# 2-RJ45.net
KiCad netlist of a schematic drawn in Altium Designer
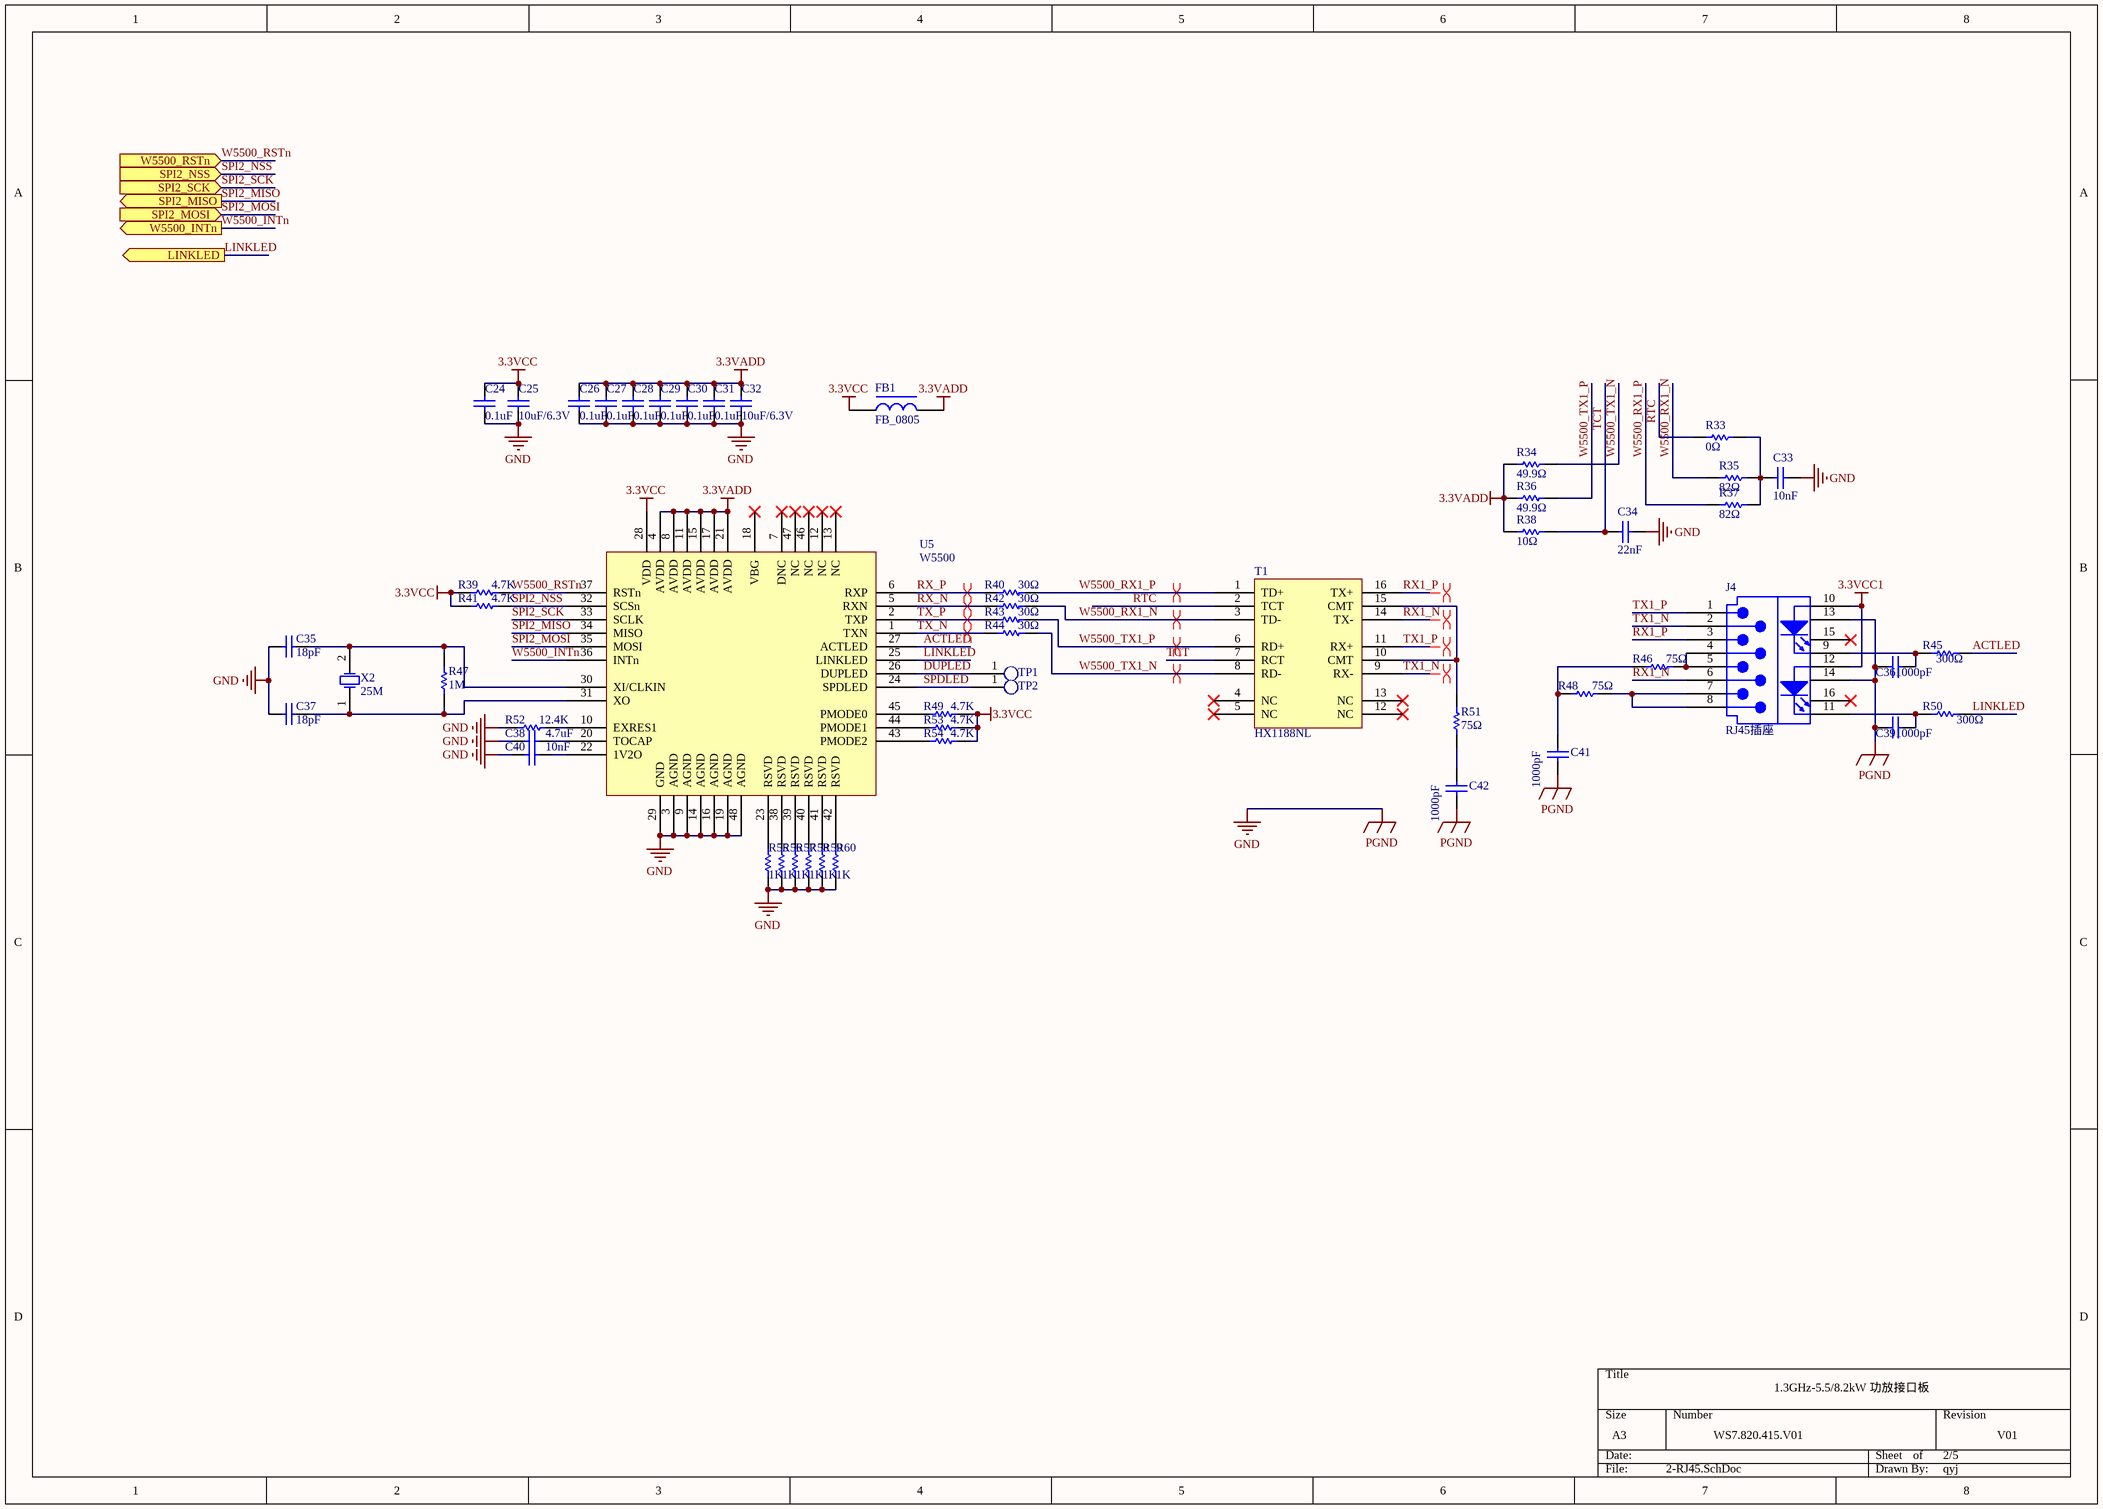
[diagram p0: 2-RJ45.SchDoc]

(export (version "E")
  (design (tool "Eeschema 10.0.6"))
  (components
    (comp (ref "C24")
      (value "0.1uF")
      (footprint "C0603")
      (description "贴片电容_GRM188R71H104KA01D_0.1uF±10%,50V,0603")
      (libsource (lib "20贴片电容0603") (part "0.1uF贴片电容"))
    )
    (comp (ref "C25")
      (value "10uF/6.3V")
      (footprint "C0603")
      (description "贴片电容_GRM188R60J106ME47D_10uF±20%,6.3V,0603")
      (libsource (lib "20贴片电容0603") (part "10uF贴片电容"))
    )
    (comp (ref "C26")
      (value "0.1uF")
      (footprint "C0603")
      (description "贴片电容_GRM188R71H104KA01D_0.1uF±10%,50V,0603")
      (libsource (lib "20贴片电容0603") (part "0.1uF贴片电容"))
    )
    (comp (ref "C27")
      (value "0.1uF")
      (footprint "C0603")
      (description "贴片电容_GRM188R71H104KA01D_0.1uF±10%,50V,0603")
      (libsource (lib "20贴片电容0603") (part "0.1uF贴片电容"))
    )
    (comp (ref "C28")
      (value "0.1uF")
      (footprint "C0603")
      (description "贴片电容_GRM188R71H104KA01D_0.1uF±10%,50V,0603")
      (libsource (lib "20贴片电容0603") (part "0.1uF贴片电容"))
    )
    (comp (ref "C29")
      (value "0.1uF")
      (footprint "C0603")
      (description "贴片电容_GRM188R71H104KA01D_0.1uF±10%,50V,0603")
      (libsource (lib "20贴片电容0603") (part "0.1uF贴片电容"))
    )
    (comp (ref "C30")
      (value "0.1uF")
      (footprint "C0603")
      (description "贴片电容_GRM188R71H104KA01D_0.1uF±10%,50V,0603")
      (libsource (lib "20贴片电容0603") (part "0.1uF贴片电容"))
    )
    (comp (ref "C31")
      (value "0.1uF")
      (footprint "C0603")
      (description "贴片电容_GRM188R71H104KA01D_0.1uF±10%,50V,0603")
      (libsource (lib "20贴片电容0603") (part "0.1uF贴片电容"))
    )
    (comp (ref "C32")
      (value "10uF/6.3V")
      (footprint "C0603")
      (description "贴片电容_GRM188R60J106ME47D_10uF±20%,6.3V,0603")
      (libsource (lib "20贴片电容0603") (part "10uF贴片电容"))
    )
    (comp (ref "C33")
      (value "10nF")
      (footprint "C0603")
      (description "C0603C103K5RAC_10nF±10%,50V,0603")
      (fields (field (name "MPN") "KEMET"))
      (libsource (lib "20贴片电容0603") (part "0.1uF贴片电容"))
    )
    (comp (ref "C34")
      (value "22nF")
      (footprint "C0603")
      (description "贴片电容_22nF±5%,50V,0603")
      (libsource (lib "20贴片电容0603") (part "27nF贴片电容"))
    )
    (comp (ref "C35")
      (value "18pF")
      (footprint "C0603")
      (description "贴片电容_GRM1885C1H180JA01D_18pF±5%,50V,0603")
      (libsource (lib "20贴片电容0603") (part "18pF贴片电容"))
    )
    (comp (ref "C36")
      (value "1000pF")
      (footprint "C0603")
      (description "贴片电容_GRM188R71H102KA01_1000pF±10%,50V,0603")
      (libsource (lib "20贴片电容0603") (part "1000pF贴片电容"))
    )
    (comp (ref "C37")
      (value "18pF")
      (footprint "C0603")
      (description "贴片电容_GRM1885C1H180JA01D_18pF±5%,50V,0603")
      (libsource (lib "20贴片电容0603") (part "18pF贴片电容"))
    )
    (comp (ref "C38")
      (value "4.7uF")
      (footprint "C0603")
      (description "GRM188R61C475K_4.7uF±10%,16V,0603")
      (fields (field (name "MPN") "Murata"))
      (libsource (lib "20贴片电容0603") (part "1uF贴片电容"))
    )
    (comp (ref "C39")
      (value "1000pF")
      (footprint "C0603")
      (description "贴片电容_GRM188R71H102KA01_1000pF±10%,50V,0603")
      (libsource (lib "20贴片电容0603") (part "1000pF贴片电容"))
    )
    (comp (ref "C40")
      (value "10nF")
      (footprint "C0603")
      (description "C0603C103K5RAC_10nF±10%,50V,0603")
      (fields (field (name "MPN") "KEMET"))
      (libsource (lib "20贴片电容0603") (part "0.1uF贴片电容"))
    )
    (comp (ref "C41")
      (value "1000pF")
      (footprint "C1206")
      (description "贴片电容_C1206C102J5GAC _1000pF±5%,50V,1206")
      (fields (field (name "MPN") "KEMET"))
      (libsource (lib "22贴片电容1210") (part "10uF贴片电容"))
    )
    (comp (ref "C42")
      (value "1000pF")
      (footprint "C1206")
      (description "贴片电容_C1206C102J5GAC _1000pF±5%,50V,1206")
      (fields (field (name "MPN") "KEMET"))
      (libsource (lib "22贴片电容1210") (part "10uF贴片电容"))
    )
    (comp (ref "FB1")
      (value "FB_0805")
      (footprint "L0805")
      (description "贴片磁珠_600R,0805")
      (libsource (lib "32贴片磁珠0805") (part "0805贴片磁珠"))
    )
    (comp (ref "J4")
      (value "RJ45插座")
      (footprint "RJ45TH-1x1-2R54-LED")
      (description "RJ45插座_1*1,带左黄右绿灯,弯脚")
      (fields (field (name "MPN") "朱迅"))
      (libsource (lib "91连接器") (part "RJ45弯脚带灯"))
    )
    (comp (ref "R33")
      (value "0Ω")
      (footprint "R0603")
      (description "贴片电阻_0Ω±5%,0603")
      (libsource (lib "10贴片电阻0603") (part "0Ω贴片电阻"))
    )
    (comp (ref "R34")
      (value "49.9Ω")
      (footprint "R0603")
      (description "贴片电阻_49.9Ω±1%,0603")
      (libsource (lib "10贴片电阻0603") (part "51Ω贴片电阻"))
    )
    (comp (ref "R35")
      (value "82Ω")
      (footprint "R0603")
      (description "贴片电阻_82Ω±1%,0603")
      (libsource (lib "10贴片电阻0603") (part "51Ω贴片电阻"))
    )
    (comp (ref "R36")
      (value "49.9Ω")
      (footprint "R0603")
      (description "贴片电阻_49.9Ω±1%,0603")
      (libsource (lib "10贴片电阻0603") (part "51Ω贴片电阻"))
    )
    (comp (ref "R37")
      (value "82Ω")
      (footprint "R0603")
      (description "贴片电阻_82Ω±1%,0603")
      (libsource (lib "10贴片电阻0603") (part "51Ω贴片电阻"))
    )
    (comp (ref "R38")
      (value "10Ω")
      (footprint "R0603")
      (description "贴片电阻_10Ω±5%,0603")
      (libsource (lib "10贴片电阻0603") (part "10Ω贴片电阻"))
    )
    (comp (ref "R39")
      (value "4.7K")
      (footprint "R0603")
      (description "贴片电阻_4.7K±5%,0603")
      (libsource (lib "10贴片电阻0603") (part "4.7K贴片电阻"))
    )
    (comp (ref "R40")
      (value "30Ω")
      (footprint "R0603")
      (description "贴片电阻_30Ω±5%,0603")
      (libsource (lib "10贴片电阻0603") (part "30Ω贴片电阻"))
    )
    (comp (ref "R41")
      (value "4.7K")
      (footprint "R0603")
      (description "贴片电阻_4.7K±5%,0603")
      (libsource (lib "10贴片电阻0603") (part "4.7K贴片电阻"))
    )
    (comp (ref "R42")
      (value "30Ω")
      (footprint "R0603")
      (description "贴片电阻_30Ω±5%,0603")
      (libsource (lib "10贴片电阻0603") (part "30Ω贴片电阻"))
    )
    (comp (ref "R43")
      (value "30Ω")
      (footprint "R0603")
      (description "贴片电阻_30Ω±5%,0603")
      (libsource (lib "10贴片电阻0603") (part "30Ω贴片电阻"))
    )
    (comp (ref "R44")
      (value "30Ω")
      (footprint "R0603")
      (description "贴片电阻_30Ω±5%,0603")
      (libsource (lib "10贴片电阻0603") (part "30Ω贴片电阻"))
    )
    (comp (ref "R45")
      (value "300Ω")
      (footprint "R0603")
      (description "贴片电阻_300Ω±5%,0603")
      (libsource (lib "10贴片电阻0603") (part "300Ω贴片电阻"))
    )
    (comp (ref "R46")
      (value "75Ω")
      (footprint "R0805")
      (description "贴片电阻_75Ω±5%,0805")
      (libsource (lib "11贴片电阻0805") (part "75Ω贴片电阻"))
    )
    (comp (ref "R47")
      (value "1M")
      (footprint "R0603")
      (description "贴片电阻_1M±5%,0603")
      (libsource (lib "10贴片电阻0603") (part "1M贴片电阻"))
    )
    (comp (ref "R48")
      (value "75Ω")
      (footprint "R0805")
      (description "贴片电阻_75Ω±5%,0805")
      (libsource (lib "11贴片电阻0805") (part "75Ω贴片电阻"))
    )
    (comp (ref "R49")
      (value "4.7K")
      (footprint "R0603")
      (description "贴片电阻_4.7K±5%,0603")
      (libsource (lib "10贴片电阻0603") (part "4.7K贴片电阻"))
    )
    (comp (ref "R50")
      (value "300Ω")
      (footprint "R0603")
      (description "贴片电阻_300Ω±5%,0603")
      (libsource (lib "10贴片电阻0603") (part "300Ω贴片电阻"))
    )
    (comp (ref "R51")
      (value "75Ω")
      (footprint "R1206")
      (description "贴片电阻_75Ω±5%,1206")
      (libsource (lib "11贴片电阻0805") (part "75Ω贴片电阻"))
    )
    (comp (ref "R52")
      (value "12.4K")
      (footprint "R0603")
      (description "贴片电阻_12.4K±1%,0603")
      (libsource (lib "10贴片电阻0603") (part "12K贴片电阻"))
    )
    (comp (ref "R53")
      (value "4.7K")
      (footprint "R0603")
      (description "贴片电阻_4.7K±5%,0603")
      (libsource (lib "10贴片电阻0603") (part "4.7K贴片电阻"))
    )
    (comp (ref "R54")
      (value "4.7K")
      (footprint "R0603")
      (description "贴片电阻_4.7K±5%,0603")
      (libsource (lib "10贴片电阻0603") (part "4.7K贴片电阻"))
    )
    (comp (ref "R55")
      (value "1K")
      (footprint "R0603")
      (description "贴片电阻_1K±5%,0603")
      (libsource (lib "10贴片电阻0603") (part "1K贴片电阻"))
    )
    (comp (ref "R56")
      (value "1K")
      (footprint "R0603")
      (description "贴片电阻_1K±5%,0603")
      (libsource (lib "10贴片电阻0603") (part "1K贴片电阻"))
    )
    (comp (ref "R57")
      (value "1K")
      (footprint "R0603")
      (description "贴片电阻_1K±5%,0603")
      (libsource (lib "10贴片电阻0603") (part "1K贴片电阻"))
    )
    (comp (ref "R58")
      (value "1K")
      (footprint "R0603")
      (description "贴片电阻_1K±5%,0603")
      (libsource (lib "10贴片电阻0603") (part "1K贴片电阻"))
    )
    (comp (ref "R59")
      (value "1K")
      (footprint "R0603")
      (description "贴片电阻_1K±5%,0603")
      (libsource (lib "10贴片电阻0603") (part "1K贴片电阻"))
    )
    (comp (ref "R60")
      (value "1K")
      (footprint "R0603")
      (description "贴片电阻_1K±5%,0603")
      (libsource (lib "10贴片电阻0603") (part "1K贴片电阻"))
    )
    (comp (ref "T1")
      (value "HX1188NL")
      (footprint "SOP16-1R27-7R11x12R7")
      (description "网络变压器_HX1188NL_百兆,SOIC16")
      (libsource (lib "89网络变压器") (part "HX1188NL"))
    )
    (comp (ref "TP1")
      (value "TEST")
      (footprint "TP0R8")
      (description "表贴测试点0.8mm")
      (libsource (lib "103其他（hole，test等）") (part "TP0.8mm"))
    )
    (comp (ref "TP2")
      (value "TEST")
      (footprint "TP0R8")
      (description "表贴测试点0.8mm")
      (libsource (lib "103其他（hole，test等）") (part "TP0.8mm"))
    )
    (comp (ref "U5")
      (value "W5500")
      (footprint "TQFN48-0R5-7X7")
      (description "以太网控制器_W5500_LQFP48")
      (libsource (lib "86网口芯片") (part "W5500"))
    )
    (comp (ref "X2")
      (value "25M")
      (footprint "CRY2SM-6R0x3R5")
      (description "贴片无源晶体_25MHz,30ppm,6035封装")
      (libsource (lib "60振荡器") (part "25M贴片无源晶体"))
    )
  )
  (nets
    (net (code "1") (name "/ACTLED") (class "Default")
      (node (ref "R45") (pin "2") (pinfunction "2_2") (pintype "passive"))
      (node (ref "U5") (pin "27") (pinfunction "ACTLED_27") (pintype "passive"))
    )
    (net (code "2") (name "/DUPLED") (class "Default")
      (node (ref "TP1") (pin "1") (pinfunction "TP_1") (pintype "passive"))
      (node (ref "U5") (pin "26") (pinfunction "DUPLED_26") (pintype "passive"))
    )
    (net (code "3") (name "/LINKLED") (class "Default")
      (node (ref "R50") (pin "2") (pinfunction "2_2") (pintype "passive"))
      (node (ref "U5") (pin "25") (pinfunction "LINKLED_25") (pintype "passive"))
    )
    (net (code "4") (name "/RTC") (class "Default")
      (node (ref "R33") (pin "2") (pinfunction "2_2") (pintype "passive"))
      (node (ref "T1") (pin "2") (pinfunction "TCT_2") (pintype "passive"))
    )
    (net (code "5") (name "/RX1_N") (class "Default")
      (node (ref "J4") (pin "6") (pinfunction "RX-_6") (pintype "passive"))
      (node (ref "T1") (pin "14") (pinfunction "TX-_14") (pintype "passive"))
    )
    (net (code "6") (name "/RX1_P") (class "Default")
      (node (ref "J4") (pin "3") (pinfunction "RX+_3") (pintype "passive"))
      (node (ref "T1") (pin "16") (pinfunction "TX+_16") (pintype "passive"))
    )
    (net (code "7") (name "/RX_N") (class "Default")
      (node (ref "R42") (pin "1") (pinfunction "1_1") (pintype "passive"))
      (node (ref "U5") (pin "5") (pinfunction "RXN_5") (pintype "passive"))
    )
    (net (code "8") (name "/RX_P") (class "Default")
      (node (ref "R40") (pin "1") (pinfunction "1_1") (pintype "passive"))
      (node (ref "U5") (pin "6") (pinfunction "RXP_6") (pintype "passive"))
    )
    (net (code "9") (name "/SPDLED") (class "Default")
      (node (ref "TP2") (pin "1") (pinfunction "TP_1") (pintype "passive"))
      (node (ref "U5") (pin "24") (pinfunction "SPDLED_24") (pintype "passive"))
    )
    (net (code "10") (name "/SPI2_MISO") (class "Default")
      (node (ref "U5") (pin "34") (pinfunction "MISO_34") (pintype "passive"))
    )
    (net (code "11") (name "/SPI2_MOSI") (class "Default")
      (node (ref "U5") (pin "35") (pinfunction "MOSI_35") (pintype "passive"))
    )
    (net (code "12") (name "/SPI2_NSS") (class "Default")
      (node (ref "R41") (pin "1") (pinfunction "1_1") (pintype "passive"))
      (node (ref "U5") (pin "32") (pinfunction "SCSn_32") (pintype "passive"))
    )
    (net (code "13") (name "/SPI2_SCK") (class "Default")
      (node (ref "U5") (pin "33") (pinfunction "SCLK_33") (pintype "passive"))
    )
    (net (code "14") (name "/TCT") (class "Default")
      (node (ref "C34") (pin "2") (pinfunction "2_2") (pintype "passive"))
      (node (ref "R38") (pin "1") (pinfunction "1_1") (pintype "passive"))
      (node (ref "T1") (pin "7") (pinfunction "RCT_7") (pintype "passive"))
    )
    (net (code "15") (name "/TX1_N") (class "Default")
      (node (ref "J4") (pin "2") (pinfunction "TX-_2") (pintype "passive"))
      (node (ref "T1") (pin "9") (pinfunction "RX-_9") (pintype "passive"))
    )
    (net (code "16") (name "/TX1_P") (class "Default")
      (node (ref "J4") (pin "1") (pinfunction "TX+_1") (pintype "passive"))
      (node (ref "T1") (pin "11") (pinfunction "RX+_11") (pintype "passive"))
    )
    (net (code "17") (name "/TX_N") (class "Default")
      (node (ref "R44") (pin "1") (pinfunction "1_1") (pintype "passive"))
      (node (ref "U5") (pin "1") (pinfunction "TXN_1") (pintype "passive"))
    )
    (net (code "18") (name "/TX_P") (class "Default")
      (node (ref "R43") (pin "1") (pinfunction "1_1") (pintype "passive"))
      (node (ref "U5") (pin "2") (pinfunction "TXP_2") (pintype "passive"))
    )
    (net (code "19") (name "/W5500_INTn") (class "Default")
      (node (ref "U5") (pin "36") (pinfunction "INTn_36") (pintype "passive"))
    )
    (net (code "20") (name "/W5500_RSTn") (class "Default")
      (node (ref "R39") (pin "1") (pinfunction "1_1") (pintype "passive"))
      (node (ref "U5") (pin "37") (pinfunction "RSTn_37") (pintype "passive"))
    )
    (net (code "21") (name "/W5500_RX1_N") (class "Default")
      (node (ref "R35") (pin "2") (pinfunction "2_2") (pintype "passive"))
      (node (ref "R42") (pin "2") (pinfunction "2_2") (pintype "passive"))
      (node (ref "T1") (pin "3") (pinfunction "TD-_3") (pintype "passive"))
    )
    (net (code "22") (name "/W5500_RX1_P") (class "Default")
      (node (ref "R37") (pin "2") (pinfunction "2_2") (pintype "passive"))
      (node (ref "R40") (pin "2") (pinfunction "2_2") (pintype "passive"))
      (node (ref "T1") (pin "1") (pinfunction "TD+_1") (pintype "passive"))
    )
    (net (code "23") (name "/W5500_TX1_N") (class "Default")
      (node (ref "R34") (pin "1") (pinfunction "1_1") (pintype "passive"))
      (node (ref "R44") (pin "2") (pinfunction "2_2") (pintype "passive"))
      (node (ref "T1") (pin "8") (pinfunction "RD-_8") (pintype "passive"))
    )
    (net (code "24") (name "/W5500_TX1_P") (class "Default")
      (node (ref "R36") (pin "1") (pinfunction "1_1") (pintype "passive"))
      (node (ref "R43") (pin "2") (pinfunction "2_2") (pintype "passive"))
      (node (ref "T1") (pin "6") (pinfunction "RD+_6") (pintype "passive"))
    )
    (net (code "25") (name "3.3VADD") (class "Default")
      (node (ref "C26") (pin "2") (pinfunction "2_2") (pintype "passive"))
      (node (ref "C27") (pin "2") (pinfunction "2_2") (pintype "passive"))
      (node (ref "C28") (pin "2") (pinfunction "2_2") (pintype "passive"))
      (node (ref "C29") (pin "2") (pinfunction "2_2") (pintype "passive"))
      (node (ref "C30") (pin "2") (pinfunction "2_2") (pintype "passive"))
      (node (ref "C31") (pin "2") (pinfunction "2_2") (pintype "passive"))
      (node (ref "C32") (pin "2") (pinfunction "2_2") (pintype "passive"))
      (node (ref "FB1") (pin "2") (pinfunction "2_2") (pintype "passive"))
      (node (ref "R34") (pin "2") (pinfunction "2_2") (pintype "passive"))
      (node (ref "R36") (pin "2") (pinfunction "2_2") (pintype "passive"))
      (node (ref "R38") (pin "2") (pinfunction "2_2") (pintype "passive"))
      (node (ref "U5") (pin "11") (pinfunction "AVDD_11") (pintype "passive"))
      (node (ref "U5") (pin "15") (pinfunction "AVDD_15") (pintype "passive"))
      (node (ref "U5") (pin "17") (pinfunction "AVDD_17") (pintype "passive"))
      (node (ref "U5") (pin "21") (pinfunction "AVDD_21") (pintype "passive"))
      (node (ref "U5") (pin "4") (pinfunction "AVDD_4") (pintype "passive"))
      (node (ref "U5") (pin "8") (pinfunction "AVDD_8") (pintype "passive"))
    )
    (net (code "26") (name "3.3VCC") (class "Default")
      (node (ref "C24") (pin "2") (pinfunction "2_2") (pintype "passive"))
      (node (ref "C25") (pin "2") (pinfunction "2_2") (pintype "passive"))
      (node (ref "FB1") (pin "1") (pinfunction "1_1") (pintype "passive"))
      (node (ref "R39") (pin "2") (pinfunction "2_2") (pintype "passive"))
      (node (ref "R41") (pin "2") (pinfunction "2_2") (pintype "passive"))
      (node (ref "R49") (pin "2") (pinfunction "2_2") (pintype "passive"))
      (node (ref "R53") (pin "2") (pinfunction "2_2") (pintype "passive"))
      (node (ref "R54") (pin "2") (pinfunction "2_2") (pintype "passive"))
      (node (ref "U5") (pin "28") (pinfunction "VDD_28") (pintype "passive"))
    )
    (net (code "27") (name "3.3VCC1") (class "Default")
      (node (ref "J4") (pin "10") (pinfunction "A1_10") (pintype "passive"))
      (node (ref "J4") (pin "12") (pinfunction "A2_12") (pintype "passive"))
    )
    (net (code "28") (name "GND") (class "Default")
      (node (ref "C24") (pin "1") (pinfunction "1_1") (pintype "passive"))
      (node (ref "C25") (pin "1") (pinfunction "1_1") (pintype "passive"))
      (node (ref "C26") (pin "1") (pinfunction "1_1") (pintype "passive"))
      (node (ref "C27") (pin "1") (pinfunction "1_1") (pintype "passive"))
      (node (ref "C28") (pin "1") (pinfunction "1_1") (pintype "passive"))
      (node (ref "C29") (pin "1") (pinfunction "1_1") (pintype "passive"))
      (node (ref "C30") (pin "1") (pinfunction "1_1") (pintype "passive"))
      (node (ref "C31") (pin "1") (pinfunction "1_1") (pintype "passive"))
      (node (ref "C32") (pin "1") (pinfunction "1_1") (pintype "passive"))
      (node (ref "C33") (pin "1") (pinfunction "1_1") (pintype "passive"))
      (node (ref "C34") (pin "1") (pinfunction "1_1") (pintype "passive"))
      (node (ref "C35") (pin "1") (pinfunction "1_1") (pintype "passive"))
      (node (ref "C36") (pin "1") (pinfunction "1_1") (pintype "passive"))
      (node (ref "C37") (pin "1") (pinfunction "1_1") (pintype "passive"))
      (node (ref "C38") (pin "1") (pinfunction "1_1") (pintype "passive"))
      (node (ref "C39") (pin "1") (pinfunction "1_1") (pintype "passive"))
      (node (ref "C40") (pin "1") (pinfunction "1_1") (pintype "passive"))
      (node (ref "C41") (pin "1") (pinfunction "1_1") (pintype "passive"))
      (node (ref "C42") (pin "1") (pinfunction "1_1") (pintype "passive"))
      (node (ref "J4") (pin "13") (pinfunction "13_13") (pintype "passive"))
      (node (ref "J4") (pin "14") (pinfunction "14_14") (pintype "passive"))
      (node (ref "R52") (pin "1") (pinfunction "1_1") (pintype "passive"))
      (node (ref "R55") (pin "1") (pinfunction "1_1") (pintype "passive"))
      (node (ref "R56") (pin "1") (pinfunction "1_1") (pintype "passive"))
      (node (ref "R57") (pin "1") (pinfunction "1_1") (pintype "passive"))
      (node (ref "R58") (pin "1") (pinfunction "1_1") (pintype "passive"))
      (node (ref "R59") (pin "1") (pinfunction "1_1") (pintype "passive"))
      (node (ref "R60") (pin "1") (pinfunction "1_1") (pintype "passive"))
      (node (ref "U5") (pin "14") (pinfunction "AGND_14") (pintype "passive"))
      (node (ref "U5") (pin "16") (pinfunction "AGND_16") (pintype "passive"))
      (node (ref "U5") (pin "19") (pinfunction "AGND_19") (pintype "passive"))
      (node (ref "U5") (pin "29") (pinfunction "GND_29") (pintype "passive"))
      (node (ref "U5") (pin "3") (pinfunction "AGND_3") (pintype "passive"))
      (node (ref "U5") (pin "48") (pinfunction "AGND_48") (pintype "passive"))
      (node (ref "U5") (pin "9") (pinfunction "AGND_9") (pintype "passive"))
    )
    (net (code "29") (name "Net-(C33-Pad2)") (class "Default")
      (node (ref "C33") (pin "2") (pinfunction "2_2") (pintype "passive"))
      (node (ref "R33") (pin "1") (pinfunction "1_1") (pintype "passive"))
      (node (ref "R35") (pin "1") (pinfunction "1_1") (pintype "passive"))
      (node (ref "R37") (pin "1") (pinfunction "1_1") (pintype "passive"))
    )
    (net (code "30") (name "Net-(C41-Pad2)") (class "Default")
      (node (ref "C41") (pin "2") (pinfunction "2_2") (pintype "passive"))
      (node (ref "R46") (pin "1") (pinfunction "1_1") (pintype "passive"))
      (node (ref "R48") (pin "1") (pinfunction "1_1") (pintype "passive"))
    )
    (net (code "31") (name "Net-(C42-Pad2)") (class "Default")
      (node (ref "C42") (pin "2") (pinfunction "2_2") (pintype "passive"))
      (node (ref "R51") (pin "1") (pinfunction "1_1") (pintype "passive"))
    )
    (net (code "32") (name "Net-(J4-K1)") (class "Default")
      (node (ref "C36") (pin "2") (pinfunction "2_2") (pintype "passive"))
      (node (ref "J4") (pin "9") (pinfunction "K1_9") (pintype "passive"))
      (node (ref "R45") (pin "1") (pinfunction "1_1") (pintype "passive"))
    )
    (net (code "33") (name "Net-(J4-K2)") (class "Default")
      (node (ref "C39") (pin "2") (pinfunction "2_2") (pintype "passive"))
      (node (ref "J4") (pin "11") (pinfunction "K2_11") (pintype "passive"))
      (node (ref "R50") (pin "1") (pinfunction "1_1") (pintype "passive"))
    )
    (net (code "34") (name "Net-(J4-NC-Pad4)") (class "Default")
      (node (ref "J4") (pin "4") (pinfunction "NC_4") (pintype "passive"))
      (node (ref "J4") (pin "5") (pinfunction "NC_5") (pintype "passive"))
      (node (ref "R46") (pin "2") (pinfunction "2_2") (pintype "passive"))
    )
    (net (code "35") (name "Net-(J4-NC-Pad7)") (class "Default")
      (node (ref "J4") (pin "7") (pinfunction "NC_7") (pintype "passive"))
      (node (ref "J4") (pin "8") (pinfunction "NC_8") (pintype "passive"))
      (node (ref "R48") (pin "2") (pinfunction "2_2") (pintype "passive"))
    )
    (net (code "36") (name "Net-(R51-Pad2)") (class "Default")
      (node (ref "R51") (pin "2") (pinfunction "2_2") (pintype "passive"))
      (node (ref "T1") (pin "10") (pinfunction "CMT_10") (pintype "passive"))
      (node (ref "T1") (pin "15") (pinfunction "CMT_15") (pintype "passive"))
    )
    (net (code "37") (name "Net-(R55-Pad2)") (class "Default")
      (node (ref "R55") (pin "2") (pinfunction "2_2") (pintype "passive"))
      (node (ref "U5") (pin "23") (pinfunction "RSVD_23") (pintype "passive"))
    )
    (net (code "38") (name "Net-(R56-Pad2)") (class "Default")
      (node (ref "R56") (pin "2") (pinfunction "2_2") (pintype "passive"))
      (node (ref "U5") (pin "38") (pinfunction "RSVD_38") (pintype "passive"))
    )
    (net (code "39") (name "Net-(R57-Pad2)") (class "Default")
      (node (ref "R57") (pin "2") (pinfunction "2_2") (pintype "passive"))
      (node (ref "U5") (pin "39") (pinfunction "RSVD_39") (pintype "passive"))
    )
    (net (code "40") (name "Net-(R58-Pad2)") (class "Default")
      (node (ref "R58") (pin "2") (pinfunction "2_2") (pintype "passive"))
      (node (ref "U5") (pin "40") (pinfunction "RSVD_40") (pintype "passive"))
    )
    (net (code "41") (name "Net-(R59-Pad2)") (class "Default")
      (node (ref "R59") (pin "2") (pinfunction "2_2") (pintype "passive"))
      (node (ref "U5") (pin "41") (pinfunction "RSVD_41") (pintype "passive"))
    )
    (net (code "42") (name "Net-(R60-Pad2)") (class "Default")
      (node (ref "R60") (pin "2") (pinfunction "2_2") (pintype "passive"))
      (node (ref "U5") (pin "42") (pinfunction "RSVD_42") (pintype "passive"))
    )
    (net (code "43") (name "Net-(U5-1V2O)") (class "Default")
      (node (ref "C40") (pin "2") (pinfunction "2_2") (pintype "passive"))
      (node (ref "U5") (pin "22") (pinfunction "1V2O_22") (pintype "passive"))
    )
    (net (code "44") (name "Net-(U5-EXRES1)") (class "Default")
      (node (ref "R52") (pin "2") (pinfunction "2_2") (pintype "passive"))
      (node (ref "U5") (pin "10") (pinfunction "EXRES1_10") (pintype "passive"))
    )
    (net (code "45") (name "Net-(U5-PMODE0)") (class "Default")
      (node (ref "R49") (pin "1") (pinfunction "1_1") (pintype "passive"))
      (node (ref "U5") (pin "45") (pinfunction "PMODE0_45") (pintype "passive"))
    )
    (net (code "46") (name "Net-(U5-PMODE1)") (class "Default")
      (node (ref "R53") (pin "1") (pinfunction "1_1") (pintype "passive"))
      (node (ref "U5") (pin "44") (pinfunction "PMODE1_44") (pintype "passive"))
    )
    (net (code "47") (name "Net-(U5-PMODE2)") (class "Default")
      (node (ref "R54") (pin "1") (pinfunction "1_1") (pintype "passive"))
      (node (ref "U5") (pin "43") (pinfunction "PMODE2_43") (pintype "passive"))
    )
    (net (code "48") (name "Net-(U5-TOCAP)") (class "Default")
      (node (ref "C38") (pin "2") (pinfunction "2_2") (pintype "passive"))
      (node (ref "U5") (pin "20") (pinfunction "TOCAP_20") (pintype "passive"))
    )
    (net (code "49") (name "Net-(U5-XI{slash}CLKIN)") (class "Default")
      (node (ref "C35") (pin "2") (pinfunction "2_2") (pintype "passive"))
      (node (ref "R47") (pin "2") (pinfunction "2_2") (pintype "passive"))
      (node (ref "U5") (pin "30") (pinfunction "XI/CLKIN_30") (pintype "passive"))
      (node (ref "X2") (pin "2") (pinfunction "OSC2_2") (pintype "passive"))
    )
    (net (code "50") (name "Net-(U5-XO)") (class "Default")
      (node (ref "C37") (pin "2") (pinfunction "2_2") (pintype "passive"))
      (node (ref "R47") (pin "1") (pinfunction "1_1") (pintype "passive"))
      (node (ref "U5") (pin "31") (pinfunction "XO_31") (pintype "passive"))
      (node (ref "X2") (pin "1") (pinfunction "OSC1_1") (pintype "passive"))
    )
    (net (code "51") (name "unconnected-(J4-Pad15)") (class "Default")
      (node (ref "J4") (pin "15") (pinfunction "15_15") (pintype "passive+no_connect"))
    )
    (net (code "52") (name "unconnected-(J4-Pad16)") (class "Default")
      (node (ref "J4") (pin "16") (pinfunction "16_16") (pintype "passive+no_connect"))
    )
    (net (code "53") (name "unconnected-(T1-NC-Pad4)") (class "Default")
      (node (ref "T1") (pin "4") (pinfunction "NC_4") (pintype "passive+no_connect"))
    )
    (net (code "54") (name "unconnected-(T1-NC-Pad5)") (class "Default")
      (node (ref "T1") (pin "5") (pinfunction "NC_5") (pintype "passive+no_connect"))
    )
    (net (code "55") (name "unconnected-(T1-NC-Pad12)") (class "Default")
      (node (ref "T1") (pin "12") (pinfunction "NC_12") (pintype "passive+no_connect"))
    )
    (net (code "56") (name "unconnected-(T1-NC-Pad13)") (class "Default")
      (node (ref "T1") (pin "13") (pinfunction "NC_13") (pintype "passive+no_connect"))
    )
    (net (code "57") (name "unconnected-(U5-DNC-Pad7)") (class "Default")
      (node (ref "U5") (pin "7") (pinfunction "DNC_7") (pintype "passive+no_connect"))
    )
    (net (code "58") (name "unconnected-(U5-NC-Pad12)") (class "Default")
      (node (ref "U5") (pin "12") (pinfunction "NC_12") (pintype "passive+no_connect"))
    )
    (net (code "59") (name "unconnected-(U5-NC-Pad13)") (class "Default")
      (node (ref "U5") (pin "13") (pinfunction "NC_13") (pintype "passive+no_connect"))
    )
    (net (code "60") (name "unconnected-(U5-NC-Pad46)") (class "Default")
      (node (ref "U5") (pin "46") (pinfunction "NC_46") (pintype "passive+no_connect"))
    )
    (net (code "61") (name "unconnected-(U5-NC-Pad47)") (class "Default")
      (node (ref "U5") (pin "47") (pinfunction "NC_47") (pintype "passive+no_connect"))
    )
    (net (code "62") (name "unconnected-(U5-VBG-Pad18)") (class "Default")
      (node (ref "U5") (pin "18") (pinfunction "VBG_18") (pintype "passive+no_connect"))
    )
  )
)
